# LM386_1.net
KiCad netlist of a schematic drawn in EasyEDA Pro
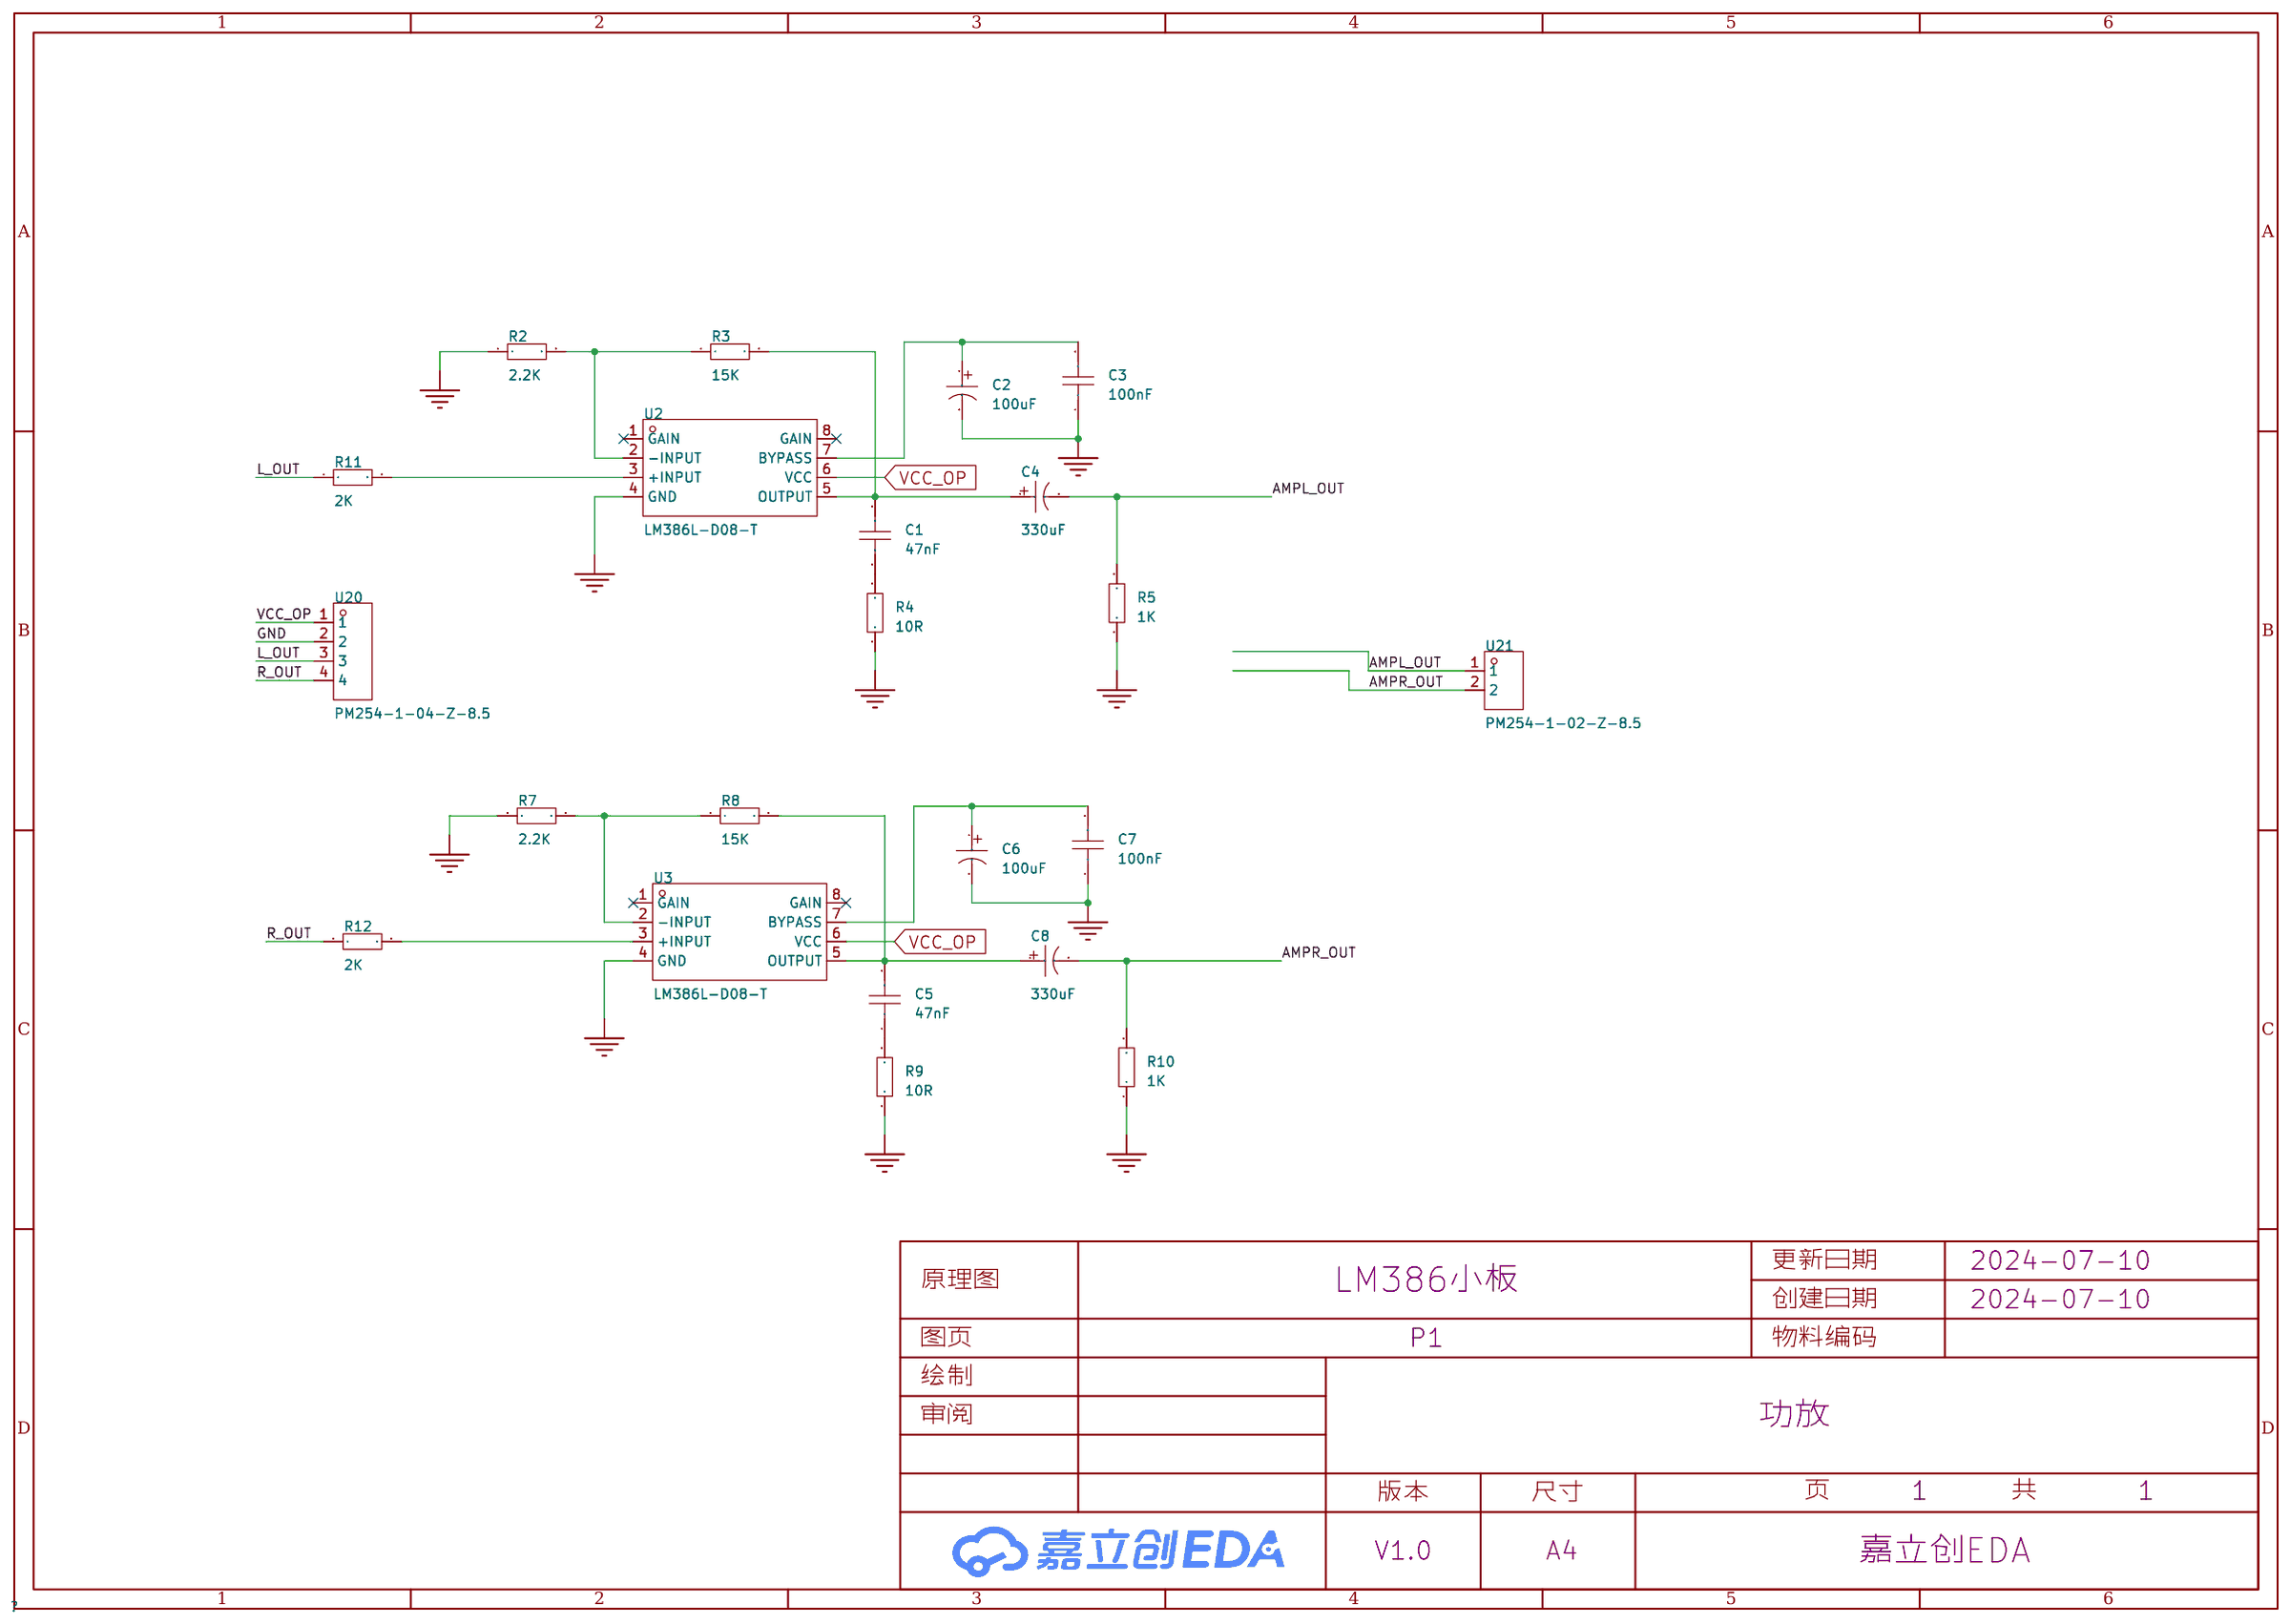
[diagram p0: schematic sheet]

(export (version "E")
  (design (tool "Eeschema 10.0.6"))
  (components
    (comp (ref "C1")
      (value "47nF")
      (footprint "easyedapro:C0603")
      (libsource (lib "easyedapro") (part "CapAcitance"))
    )
    (comp (ref "C2")
      (value "100uF")
      (fields (field (name "Manufacturer Part") "TAJD107K016RNJ") (field (name "Manufacturer") "Kyocera AVX"))
      (libsource (lib "easyedapro") (part "ERS1VM101E12OT"))
    )
    (comp (ref "C3")
      (value "100nF")
      (footprint "easyedapro:C0603")
      (libsource (lib "easyedapro") (part "CapAcitance"))
    )
    (comp (ref "C4")
      (value "330uF")
      (fields (field (name "Manufacturer Part") "TAJD337K010RNJ") (field (name "Manufacturer") "Kyocera AVX"))
      (libsource (lib "easyedapro") (part "ERS1VM101E12OT"))
    )
    (comp (ref "C5")
      (value "47nF")
      (footprint "easyedapro:C0603")
      (libsource (lib "easyedapro") (part "CapAcitance"))
    )
    (comp (ref "C6")
      (value "100uF")
      (fields (field (name "Manufacturer Part") "TAJD107K016RNJ") (field (name "Manufacturer") "Kyocera AVX"))
      (libsource (lib "easyedapro") (part "ERS1VM101E12OT"))
    )
    (comp (ref "C7")
      (value "100nF")
      (footprint "easyedapro:C0603")
      (libsource (lib "easyedapro") (part "CapAcitance"))
    )
    (comp (ref "C8")
      (value "330uF")
      (fields (field (name "Manufacturer Part") "TAJD337K010RNJ") (field (name "Manufacturer") "Kyocera AVX"))
      (libsource (lib "easyedapro") (part "ERS1VM101E12OT"))
    )
    (comp (ref "R2") (value "2.2K") (footprint "easyedapro:R0603") (libsource (lib "easyedapro") (part "电阻")))
    (comp (ref "R3") (value "15K") (footprint "easyedapro:R0603") (libsource (lib "easyedapro") (part "电阻")))
    (comp (ref "R4") (value "10R") (footprint "easyedapro:R0603") (libsource (lib "easyedapro") (part "电阻")))
    (comp (ref "R5") (value "1K") (footprint "easyedapro:R0603") (libsource (lib "easyedapro") (part "电阻")))
    (comp (ref "R7") (value "2.2K") (footprint "easyedapro:R0603") (libsource (lib "easyedapro") (part "电阻")))
    (comp (ref "R8") (value "15K") (footprint "easyedapro:R0603") (libsource (lib "easyedapro") (part "电阻")))
    (comp (ref "R9") (value "10R") (footprint "easyedapro:R0603") (libsource (lib "easyedapro") (part "电阻")))
    (comp (ref "R10") (value "1K") (footprint "easyedapro:R0603") (libsource (lib "easyedapro") (part "电阻")))
    (comp (ref "R11") (value "2K") (footprint "easyedapro:R0603") (libsource (lib "easyedapro") (part "电阻")))
    (comp (ref "R12") (value "2K") (footprint "easyedapro:R0603") (libsource (lib "easyedapro") (part "电阻")))
    (comp (ref "U2")
      (value "LM386L-D08-T")
      (footprint "easyedapro:DIP-8_L9.7-W6.4-P2.54-LS7.6-BL")
      (description "功放类型:-;扬声器通道数:单声道;输出功率:700mWx1@8Ω;")
      (fields (field (name "Manufacturer") "UTC(友顺)"))
      (libsource (lib "easyedapro") (part "LM386L-2-D08-T"))
    )
    (comp (ref "U3")
      (value "LM386L-D08-T")
      (footprint "easyedapro:DIP-8_L9.7-W6.4-P2.54-LS7.6-BL")
      (description "功放类型:-;扬声器通道数:单声道;输出功率:700mWx1@8Ω;")
      (fields (field (name "Manufacturer") "UTC(友顺)"))
      (libsource (lib "easyedapro") (part "LM386L-2-D08-T"))
    )
    (comp (ref "U20")
      (value "PM254-1-04-Z-8.5")
      (footprint "easyedapro:HDR-TH_4P-P2.54-V-F")
      (fields (field (name "Manufacturer") "HCTL(华灿天禄)"))
      (libsource (lib "easyedapro") (part "PM254-1-04-Z-8.5"))
    )
    (comp (ref "U21")
      (value "PM254-1-02-Z-8.5")
      (footprint "easyedapro:HDR-TH_2P-P2.54-V-F")
      (fields (field (name "Manufacturer") "HCTL(华灿天禄)"))
      (libsource (lib "easyedapro") (part "PM254-1-02-Z-8.5"))
    )
  )
  (nets
    (net (code "1") (name "/AMPL_OUT") (class "Default")
      (node (ref "C4") (pin "2") (pinfunction "2_2") (pintype "input"))
      (node (ref "R5") (pin "2") (pinfunction "2_2") (pintype "input"))
      (node (ref "U21") (pin "1") (pinfunction "1_1") (pintype "unspecified"))
    )
    (net (code "2") (name "/AMPR_OUT") (class "Default")
      (node (ref "C8") (pin "2") (pinfunction "2_2") (pintype "input"))
      (node (ref "R10") (pin "2") (pinfunction "2_2") (pintype "input"))
      (node (ref "U21") (pin "2") (pinfunction "2_2") (pintype "unspecified"))
    )
    (net (code "3") (name "/L_OUT") (class "Default")
      (node (ref "R11") (pin "1") (pinfunction "1_1") (pintype "input"))
      (node (ref "U20") (pin "3") (pinfunction "3_3") (pintype "unspecified"))
    )
    (net (code "4") (name "/R_OUT") (class "Default")
      (node (ref "R12") (pin "1") (pinfunction "1_1") (pintype "input"))
      (node (ref "U20") (pin "4") (pinfunction "4_4") (pintype "unspecified"))
    )
    (net (code "5") (name "GND") (class "Default")
      (node (ref "C2") (pin "2") (pinfunction "2_2") (pintype "input"))
      (node (ref "C3") (pin "1") (pinfunction "1_1") (pintype "input"))
      (node (ref "C6") (pin "2") (pinfunction "2_2") (pintype "input"))
      (node (ref "C7") (pin "1") (pinfunction "1_1") (pintype "input"))
      (node (ref "R10") (pin "1") (pinfunction "1_1") (pintype "input"))
      (node (ref "R2") (pin "1") (pinfunction "1_1") (pintype "input"))
      (node (ref "R4") (pin "1") (pinfunction "1_1") (pintype "input"))
      (node (ref "R5") (pin "1") (pinfunction "1_1") (pintype "input"))
      (node (ref "R7") (pin "1") (pinfunction "1_1") (pintype "input"))
      (node (ref "R9") (pin "1") (pinfunction "1_1") (pintype "input"))
      (node (ref "U2") (pin "4") (pinfunction "GND_4") (pintype "input"))
      (node (ref "U20") (pin "2") (pinfunction "2_2") (pintype "unspecified"))
      (node (ref "U3") (pin "4") (pinfunction "GND_4") (pintype "input"))
    )
    (net (code "6") (name "Net-(C1-Pad1)") (class "Default")
      (node (ref "C1") (pin "1") (pinfunction "1_1") (pintype "input"))
      (node (ref "R4") (pin "2") (pinfunction "2_2") (pintype "input"))
    )
    (net (code "7") (name "Net-(C5-Pad1)") (class "Default")
      (node (ref "C5") (pin "1") (pinfunction "1_1") (pintype "input"))
      (node (ref "R9") (pin "2") (pinfunction "2_2") (pintype "input"))
    )
    (net (code "8") (name "Net-(U2-+INPUT)") (class "Default")
      (node (ref "R11") (pin "2") (pinfunction "2_2") (pintype "input"))
      (node (ref "U2") (pin "3") (pinfunction "+INPUT_3") (pintype "input"))
    )
    (net (code "9") (name "Net-(U2--INPUT)") (class "Default")
      (node (ref "R2") (pin "2") (pinfunction "2_2") (pintype "input"))
      (node (ref "R3") (pin "1") (pinfunction "1_1") (pintype "input"))
      (node (ref "U2") (pin "2") (pinfunction "-INPUT_2") (pintype "input"))
    )
    (net (code "10") (name "Net-(U2-BYPASS)") (class "Default")
      (node (ref "C2") (pin "1") (pinfunction "1_1") (pintype "input"))
      (node (ref "C3") (pin "2") (pinfunction "2_2") (pintype "input"))
      (node (ref "U2") (pin "7") (pinfunction "BYPASS_7") (pintype "input"))
    )
    (net (code "11") (name "Net-(U2-OUTPUT)") (class "Default")
      (node (ref "C1") (pin "2") (pinfunction "2_2") (pintype "input"))
      (node (ref "C4") (pin "1") (pinfunction "1_1") (pintype "input"))
      (node (ref "R3") (pin "2") (pinfunction "2_2") (pintype "input"))
      (node (ref "U2") (pin "5") (pinfunction "OUTPUT_5") (pintype "input"))
    )
    (net (code "12") (name "Net-(U3-+INPUT)") (class "Default")
      (node (ref "R12") (pin "2") (pinfunction "2_2") (pintype "input"))
      (node (ref "U3") (pin "3") (pinfunction "+INPUT_3") (pintype "input"))
    )
    (net (code "13") (name "Net-(U3--INPUT)") (class "Default")
      (node (ref "R7") (pin "2") (pinfunction "2_2") (pintype "input"))
      (node (ref "R8") (pin "1") (pinfunction "1_1") (pintype "input"))
      (node (ref "U3") (pin "2") (pinfunction "-INPUT_2") (pintype "input"))
    )
    (net (code "14") (name "Net-(U3-BYPASS)") (class "Default")
      (node (ref "C6") (pin "1") (pinfunction "1_1") (pintype "input"))
      (node (ref "C7") (pin "2") (pinfunction "2_2") (pintype "input"))
      (node (ref "U3") (pin "7") (pinfunction "BYPASS_7") (pintype "input"))
    )
    (net (code "15") (name "Net-(U3-OUTPUT)") (class "Default")
      (node (ref "C5") (pin "2") (pinfunction "2_2") (pintype "input"))
      (node (ref "C8") (pin "1") (pinfunction "1_1") (pintype "input"))
      (node (ref "R8") (pin "2") (pinfunction "2_2") (pintype "input"))
      (node (ref "U3") (pin "5") (pinfunction "OUTPUT_5") (pintype "input"))
    )
    (net (code "16") (name "VCC_OP") (class "Default")
      (node (ref "U2") (pin "6") (pinfunction "VCC_6") (pintype "input"))
      (node (ref "U20") (pin "1") (pinfunction "1_1") (pintype "unspecified"))
      (node (ref "U3") (pin "6") (pinfunction "VCC_6") (pintype "input"))
    )
    (net (code "17") (name "unconnected-(U2-GAIN-Pad1)") (class "Default")
      (node (ref "U2") (pin "1") (pinfunction "GAIN_1") (pintype "input+no_connect"))
    )
    (net (code "18") (name "unconnected-(U2-GAIN-Pad8)") (class "Default")
      (node (ref "U2") (pin "8") (pinfunction "GAIN_8") (pintype "input+no_connect"))
    )
    (net (code "19") (name "unconnected-(U3-GAIN-Pad1)") (class "Default")
      (node (ref "U3") (pin "1") (pinfunction "GAIN_1") (pintype "input+no_connect"))
    )
    (net (code "20") (name "unconnected-(U3-GAIN-Pad8)") (class "Default")
      (node (ref "U3") (pin "8") (pinfunction "GAIN_8") (pintype "input+no_connect"))
    )
  )
)
